# ModuleThermistorVoltageSenseBoard-1.net
KiCad netlist of a schematic drawn in EAGLE
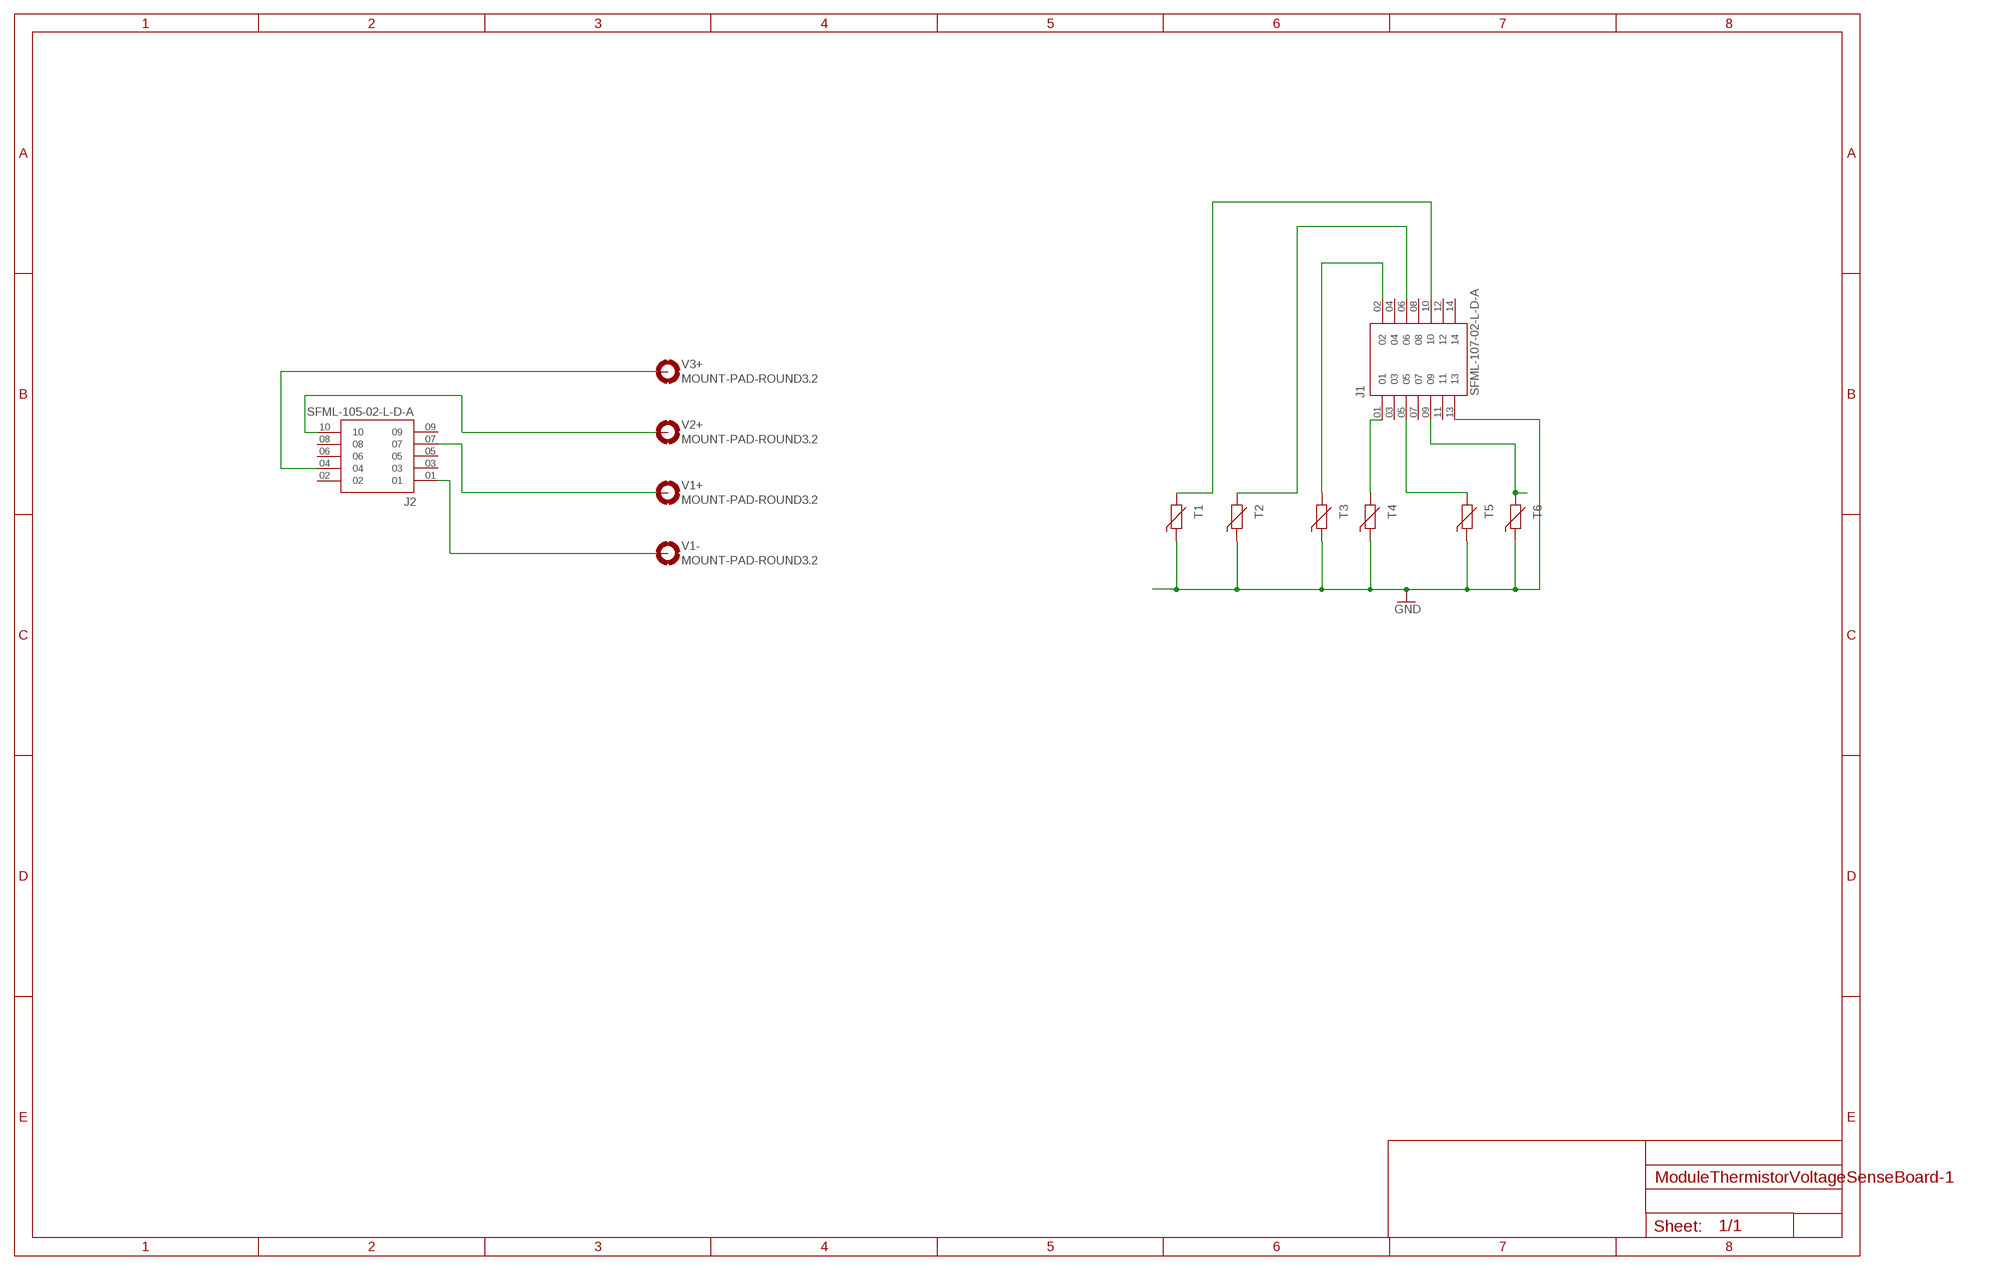
[diagram p0: schematic, sheet 1]

(export (version "E")
  (design (tool "Eeschema 10.0.6"))
  (components
    (comp (ref "J1")
      (value "SFML-107-02-L-D-A")
      (footprint "eagle-import:SAMTEC_SFML-107-02-L-D-A")
      (fields (field (name "MF") "Samtec"))
      (libsource (lib "eagle-import") (part "SFML-107-02-L-D-A"))
    )
    (comp (ref "J2")
      (value "SFML-105-02-L-D-A")
      (footprint "eagle-import:SAMTEC_SFML-105-02-L-D-A")
      (fields (field (name "MF") "Samtec"))
      (libsource (lib "eagle-import") (part "SFML-105-02-L-D-A"))
    )
    (comp (ref "T1")
      (value "THERMISTOR")
      (footprint "eagle-import:THERMISTOR_CUTOUT")
      (libsource (lib "eagle-import") (part "THERMISTOR"))
    )
    (comp (ref "T2")
      (value "THERMISTOR")
      (footprint "eagle-import:THERMISTOR_CUTOUT")
      (libsource (lib "eagle-import") (part "THERMISTOR"))
    )
    (comp (ref "T3")
      (value "THERMISTOR")
      (footprint "eagle-import:THERMISTOR_CUTOUT")
      (libsource (lib "eagle-import") (part "THERMISTOR"))
    )
    (comp (ref "T4")
      (value "THERMISTOR")
      (footprint "eagle-import:THERMISTOR_CUTOUT")
      (libsource (lib "eagle-import") (part "THERMISTOR"))
    )
    (comp (ref "T5")
      (value "THERMISTOR")
      (footprint "eagle-import:THERMISTOR_CUTOUT")
      (libsource (lib "eagle-import") (part "THERMISTOR"))
    )
    (comp (ref "T6")
      (value "THERMISTOR")
      (footprint "eagle-import:THERMISTOR_CUTOUT")
      (libsource (lib "eagle-import") (part "THERMISTOR"))
    )
    (comp (ref "V1+")
      (value "MOUNT-PAD-ROUND3.2")
      (footprint "eagle-import:3,2-PAD")
      (libsource (lib "eagle-import") (part "MOUNT-PAD-ROUND3.2"))
    )
    (comp (ref "V1-")
      (value "MOUNT-PAD-ROUND3.2")
      (footprint "eagle-import:3,2-PAD")
      (libsource (lib "eagle-import") (part "MOUNT-PAD-ROUND3.2"))
    )
    (comp (ref "V2+")
      (value "MOUNT-PAD-ROUND3.2")
      (footprint "eagle-import:3,2-PAD")
      (libsource (lib "eagle-import") (part "MOUNT-PAD-ROUND3.2"))
    )
    (comp (ref "V3+")
      (value "MOUNT-PAD-ROUND3.2")
      (footprint "eagle-import:3,2-PAD")
      (libsource (lib "eagle-import") (part "MOUNT-PAD-ROUND3.2"))
    )
  )
  (nets
    (net (code "1") (name "GND") (class "Default")
      (node (ref "J1") (pin "13") (pinfunction "13_13") (pintype "passive"))
      (node (ref "T1") (pin "1") (pinfunction "1_1") (pintype "passive"))
      (node (ref "T2") (pin "1") (pinfunction "1_1") (pintype "passive"))
      (node (ref "T3") (pin "1") (pinfunction "1_1") (pintype "passive"))
      (node (ref "T4") (pin "1") (pinfunction "1_1") (pintype "passive"))
      (node (ref "T5") (pin "1") (pinfunction "1_1") (pintype "passive"))
      (node (ref "T6") (pin "1") (pinfunction "1_1") (pintype "passive"))
    )
    (net (code "2") (name "Net-(J1-Pad01)") (class "Default")
      (node (ref "J1") (pin "01") (pinfunction "01_01") (pintype "passive"))
      (node (ref "T4") (pin "2") (pinfunction "2_2") (pintype "passive"))
    )
    (net (code "3") (name "Net-(J1-Pad02)") (class "Default")
      (node (ref "J1") (pin "02") (pinfunction "02_02") (pintype "passive"))
      (node (ref "T3") (pin "2") (pinfunction "2_2") (pintype "passive"))
    )
    (net (code "4") (name "Net-(J1-Pad05)") (class "Default")
      (node (ref "J1") (pin "05") (pinfunction "05_05") (pintype "passive"))
      (node (ref "T5") (pin "2") (pinfunction "2_2") (pintype "passive"))
    )
    (net (code "5") (name "Net-(J1-Pad06)") (class "Default")
      (node (ref "J1") (pin "06") (pinfunction "06_06") (pintype "passive"))
      (node (ref "T2") (pin "2") (pinfunction "2_2") (pintype "passive"))
    )
    (net (code "6") (name "Net-(J1-Pad09)") (class "Default")
      (node (ref "J1") (pin "09") (pinfunction "09_09") (pintype "passive"))
      (node (ref "T6") (pin "2") (pinfunction "2_2") (pintype "passive"))
    )
    (net (code "7") (name "Net-(J1-Pad10)") (class "Default")
      (node (ref "J1") (pin "10") (pinfunction "10_10") (pintype "passive"))
      (node (ref "T1") (pin "2") (pinfunction "2_2") (pintype "passive"))
    )
    (net (code "8") (name "Net-(V1+-MOUNT)") (class "Default")
      (node (ref "J2") (pin "07") (pinfunction "07_07") (pintype "passive"))
      (node (ref "V1+") (pin "B3,2") (pinfunction "MOUNT_B3,2") (pintype "passive"))
    )
    (net (code "9") (name "Net-(V1--MOUNT)") (class "Default")
      (node (ref "J2") (pin "01") (pinfunction "01_01") (pintype "passive"))
      (node (ref "V1-") (pin "B3,2") (pinfunction "MOUNT_B3,2") (pintype "passive"))
    )
    (net (code "10") (name "Net-(V2+-MOUNT)") (class "Default")
      (node (ref "J2") (pin "10") (pinfunction "10_10") (pintype "passive"))
      (node (ref "V2+") (pin "B3,2") (pinfunction "MOUNT_B3,2") (pintype "passive"))
    )
    (net (code "11") (name "Net-(V3+-MOUNT)") (class "Default")
      (node (ref "J2") (pin "04") (pinfunction "04_04") (pintype "passive"))
      (node (ref "V3+") (pin "B3,2") (pinfunction "MOUNT_B3,2") (pintype "passive"))
    )
    (net (code "12") (name "unconnected-(J1-Pad03)") (class "Default")
      (node (ref "J1") (pin "03") (pinfunction "03_03") (pintype "passive"))
    )
    (net (code "13") (name "unconnected-(J1-Pad04)") (class "Default")
      (node (ref "J1") (pin "04") (pinfunction "04_04") (pintype "passive"))
    )
    (net (code "14") (name "unconnected-(J1-Pad07)") (class "Default")
      (node (ref "J1") (pin "07") (pinfunction "07_07") (pintype "passive"))
    )
    (net (code "15") (name "unconnected-(J1-Pad08)") (class "Default")
      (node (ref "J1") (pin "08") (pinfunction "08_08") (pintype "passive"))
    )
    (net (code "16") (name "unconnected-(J1-Pad11)") (class "Default")
      (node (ref "J1") (pin "11") (pinfunction "11_11") (pintype "passive"))
    )
    (net (code "17") (name "unconnected-(J1-Pad12)") (class "Default")
      (node (ref "J1") (pin "12") (pinfunction "12_12") (pintype "passive"))
    )
    (net (code "18") (name "unconnected-(J1-Pad14)") (class "Default")
      (node (ref "J1") (pin "14") (pinfunction "14_14") (pintype "passive"))
    )
    (net (code "19") (name "unconnected-(J2-Pad02)") (class "Default")
      (node (ref "J2") (pin "02") (pinfunction "02_02") (pintype "passive"))
    )
    (net (code "20") (name "unconnected-(J2-Pad03)") (class "Default")
      (node (ref "J2") (pin "03") (pinfunction "03_03") (pintype "passive"))
    )
    (net (code "21") (name "unconnected-(J2-Pad05)") (class "Default")
      (node (ref "J2") (pin "05") (pinfunction "05_05") (pintype "passive"))
    )
    (net (code "22") (name "unconnected-(J2-Pad06)") (class "Default")
      (node (ref "J2") (pin "06") (pinfunction "06_06") (pintype "passive"))
    )
    (net (code "23") (name "unconnected-(J2-Pad08)") (class "Default")
      (node (ref "J2") (pin "08") (pinfunction "08_08") (pintype "passive"))
    )
    (net (code "24") (name "unconnected-(J2-Pad09)") (class "Default")
      (node (ref "J2") (pin "09") (pinfunction "09_09") (pintype "passive"))
    )
  )
)
